# pcb-pick-plaz-feeder-wiring.net
KiCad netlist of a schematic drawn in EAGLE
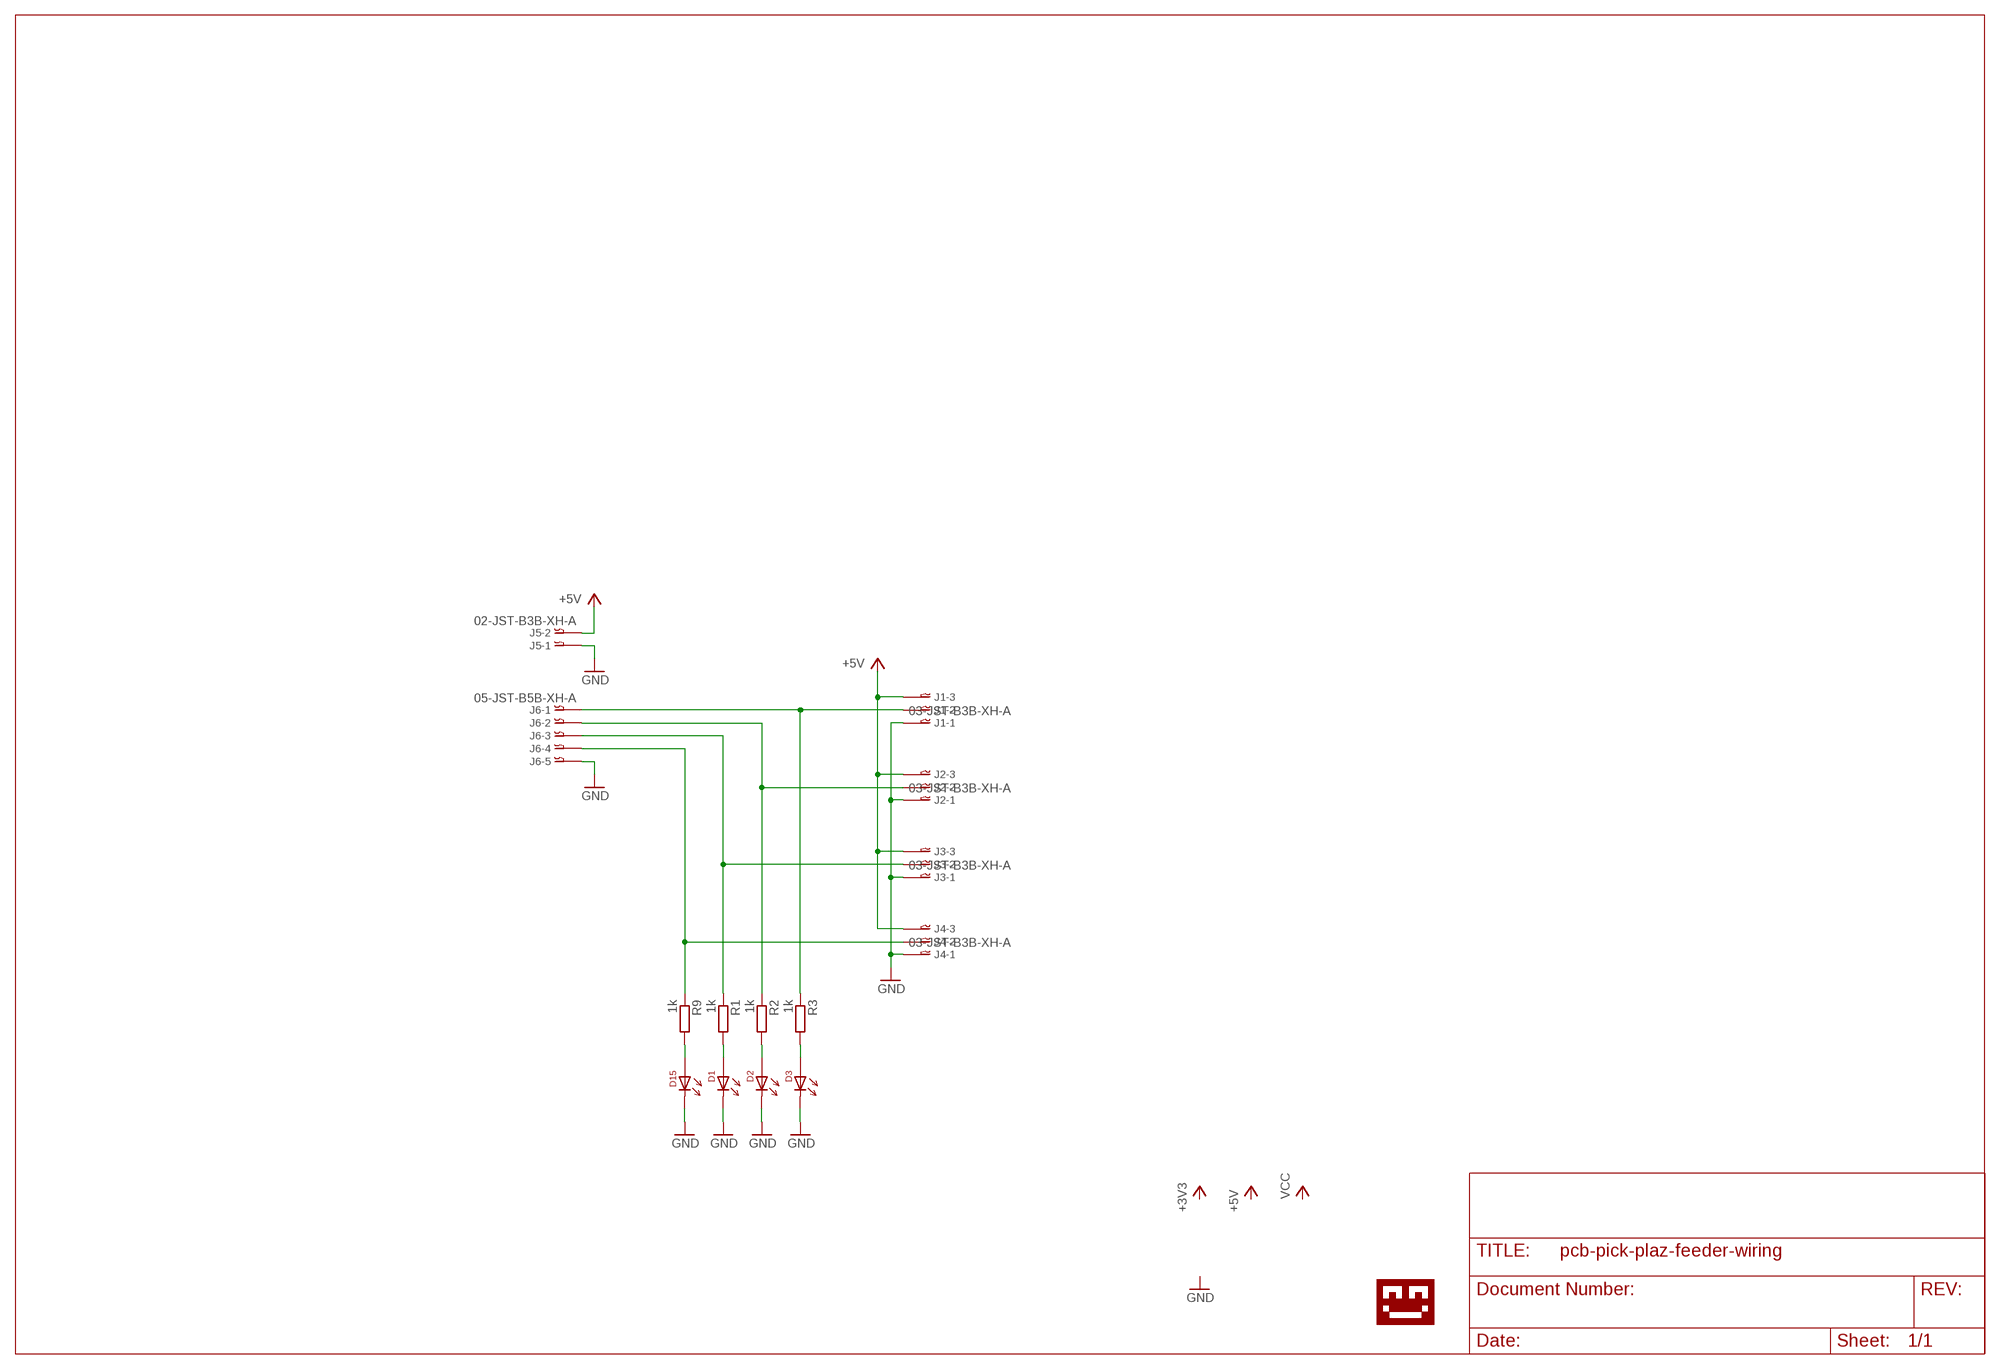
[diagram p0: schematic, sheet 1]

(export (version "E")
  (design (tool "Eeschema 10.0.6"))
  (components
    (comp (ref "D1")
      (value "LED-0805")
      (footprint "eagle-import:0805-DOT")
      (libsource (lib "eagle-import") (part "LED-0805"))
    )
    (comp (ref "D2")
      (value "LED-0805")
      (footprint "eagle-import:0805-DOT")
      (libsource (lib "eagle-import") (part "LED-0805"))
    )
    (comp (ref "D3")
      (value "LED-0805")
      (footprint "eagle-import:0805-DOT")
      (libsource (lib "eagle-import") (part "LED-0805"))
    )
    (comp (ref "D15")
      (value "LED-0805")
      (footprint "eagle-import:0805-DOT")
      (libsource (lib "eagle-import") (part "LED-0805"))
    )
    (comp (ref "J1")
      (value "03-JST-B3B-XH-A")
      (footprint "eagle-import:B3B-XH")
      (libsource (lib "eagle-import") (part "03-JST-B3B-XH-A"))
    )
    (comp (ref "J2")
      (value "03-JST-B3B-XH-A")
      (footprint "eagle-import:B3B-XH")
      (libsource (lib "eagle-import") (part "03-JST-B3B-XH-A"))
    )
    (comp (ref "J3")
      (value "03-JST-B3B-XH-A")
      (footprint "eagle-import:B3B-XH")
      (libsource (lib "eagle-import") (part "03-JST-B3B-XH-A"))
    )
    (comp (ref "J4")
      (value "03-JST-B3B-XH-A")
      (footprint "eagle-import:B3B-XH")
      (libsource (lib "eagle-import") (part "03-JST-B3B-XH-A"))
    )
    (comp (ref "J5")
      (value "02-JST-B3B-XH-A")
      (footprint "eagle-import:B2B-XH")
      (libsource (lib "eagle-import") (part "02-JST-B3B-XH-A"))
    )
    (comp (ref "J6")
      (value "05-JST-B5B-XH-A")
      (footprint "eagle-import:B5B-XH")
      (libsource (lib "eagle-import") (part "05-JST-B5B-XH-A"))
    )
    (comp (ref "R1")
      (value "1k")
      (footprint "eagle-import:0603-RES")
      (libsource (lib "eagle-import") (part "RESISTOR0603_RES"))
    )
    (comp (ref "R2")
      (value "1k")
      (footprint "eagle-import:0603-RES")
      (libsource (lib "eagle-import") (part "RESISTOR0603_RES"))
    )
    (comp (ref "R3")
      (value "1k")
      (footprint "eagle-import:0603-RES")
      (libsource (lib "eagle-import") (part "RESISTOR0603_RES"))
    )
    (comp (ref "R9")
      (value "1k")
      (footprint "eagle-import:0603-RES")
      (libsource (lib "eagle-import") (part "RESISTOR0603_RES"))
    )
    (comp (ref "U$1")
      (value "LOGO-TOBENG-1MM-FINISH")
      (footprint "eagle-import:TOBENG-1MM-FINISH")
      (libsource (lib "eagle-import") (part "LOGO-TOBENG-1MM-FINISH"))
    )
  )
  (nets
    (net (code "2") (name "+5V") (class "Default")
      (node (ref "J1") (pin "P$3") (pinfunction "1_P$3") (pintype "passive"))
      (node (ref "J2") (pin "P$3") (pinfunction "1_P$3") (pintype "passive"))
      (node (ref "J3") (pin "P$3") (pinfunction "1_P$3") (pintype "passive"))
      (node (ref "J4") (pin "P$3") (pinfunction "1_P$3") (pintype "passive"))
      (node (ref "J5") (pin "P$2") (pinfunction "1_P$2") (pintype "passive"))
    )
    (net (code "3") (name "GND") (class "Default")
      (node (ref "D1") (pin "2") (pinfunction "2_2") (pintype "bidirectional"))
      (node (ref "D15") (pin "2") (pinfunction "2_2") (pintype "bidirectional"))
      (node (ref "D2") (pin "2") (pinfunction "2_2") (pintype "bidirectional"))
      (node (ref "D3") (pin "2") (pinfunction "2_2") (pintype "bidirectional"))
      (node (ref "J1") (pin "P$1") (pinfunction "1_P$1") (pintype "passive"))
      (node (ref "J2") (pin "P$1") (pinfunction "1_P$1") (pintype "passive"))
      (node (ref "J3") (pin "P$1") (pinfunction "1_P$1") (pintype "passive"))
      (node (ref "J4") (pin "P$1") (pinfunction "1_P$1") (pintype "passive"))
      (node (ref "J5") (pin "P$1") (pinfunction "1_P$1") (pintype "passive"))
      (node (ref "J6") (pin "P$5") (pinfunction "1_P$5") (pintype "passive"))
    )
    (net (code "4") (name "Net-(D1-Pad1)") (class "Default")
      (node (ref "D1") (pin "1") (pinfunction "1_1") (pintype "bidirectional"))
      (node (ref "R1") (pin "2") (pinfunction "2_2") (pintype "passive"))
    )
    (net (code "5") (name "Net-(D2-Pad1)") (class "Default")
      (node (ref "D2") (pin "1") (pinfunction "1_1") (pintype "bidirectional"))
      (node (ref "R2") (pin "2") (pinfunction "2_2") (pintype "passive"))
    )
    (net (code "6") (name "Net-(D3-Pad1)") (class "Default")
      (node (ref "D3") (pin "1") (pinfunction "1_1") (pintype "bidirectional"))
      (node (ref "R3") (pin "2") (pinfunction "2_2") (pintype "passive"))
    )
    (net (code "7") (name "Net-(D15-Pad1)") (class "Default")
      (node (ref "D15") (pin "1") (pinfunction "1_1") (pintype "bidirectional"))
      (node (ref "R9") (pin "2") (pinfunction "2_2") (pintype "passive"))
    )
    (net (code "8") (name "Net-(J1B-1)") (class "Default")
      (node (ref "J1") (pin "P$2") (pinfunction "1_P$2") (pintype "passive"))
      (node (ref "J6") (pin "P$1") (pinfunction "1_P$1") (pintype "passive"))
      (node (ref "R3") (pin "1") (pinfunction "1_1") (pintype "passive"))
    )
    (net (code "9") (name "Net-(J2B-1)") (class "Default")
      (node (ref "J2") (pin "P$2") (pinfunction "1_P$2") (pintype "passive"))
      (node (ref "J6") (pin "P$2") (pinfunction "1_P$2") (pintype "passive"))
      (node (ref "R2") (pin "1") (pinfunction "1_1") (pintype "passive"))
    )
    (net (code "10") (name "Net-(J3B-1)") (class "Default")
      (node (ref "J3") (pin "P$2") (pinfunction "1_P$2") (pintype "passive"))
      (node (ref "J6") (pin "P$3") (pinfunction "1_P$3") (pintype "passive"))
      (node (ref "R1") (pin "1") (pinfunction "1_1") (pintype "passive"))
    )
    (net (code "11") (name "Net-(J4B-1)") (class "Default")
      (node (ref "J4") (pin "P$2") (pinfunction "1_P$2") (pintype "passive"))
      (node (ref "J6") (pin "P$4") (pinfunction "1_P$4") (pintype "passive"))
      (node (ref "R9") (pin "1") (pinfunction "1_1") (pintype "passive"))
    )
  )
)
